# montaj_electric_nou.net
KiCad netlist of a schematic drawn in EAGLE
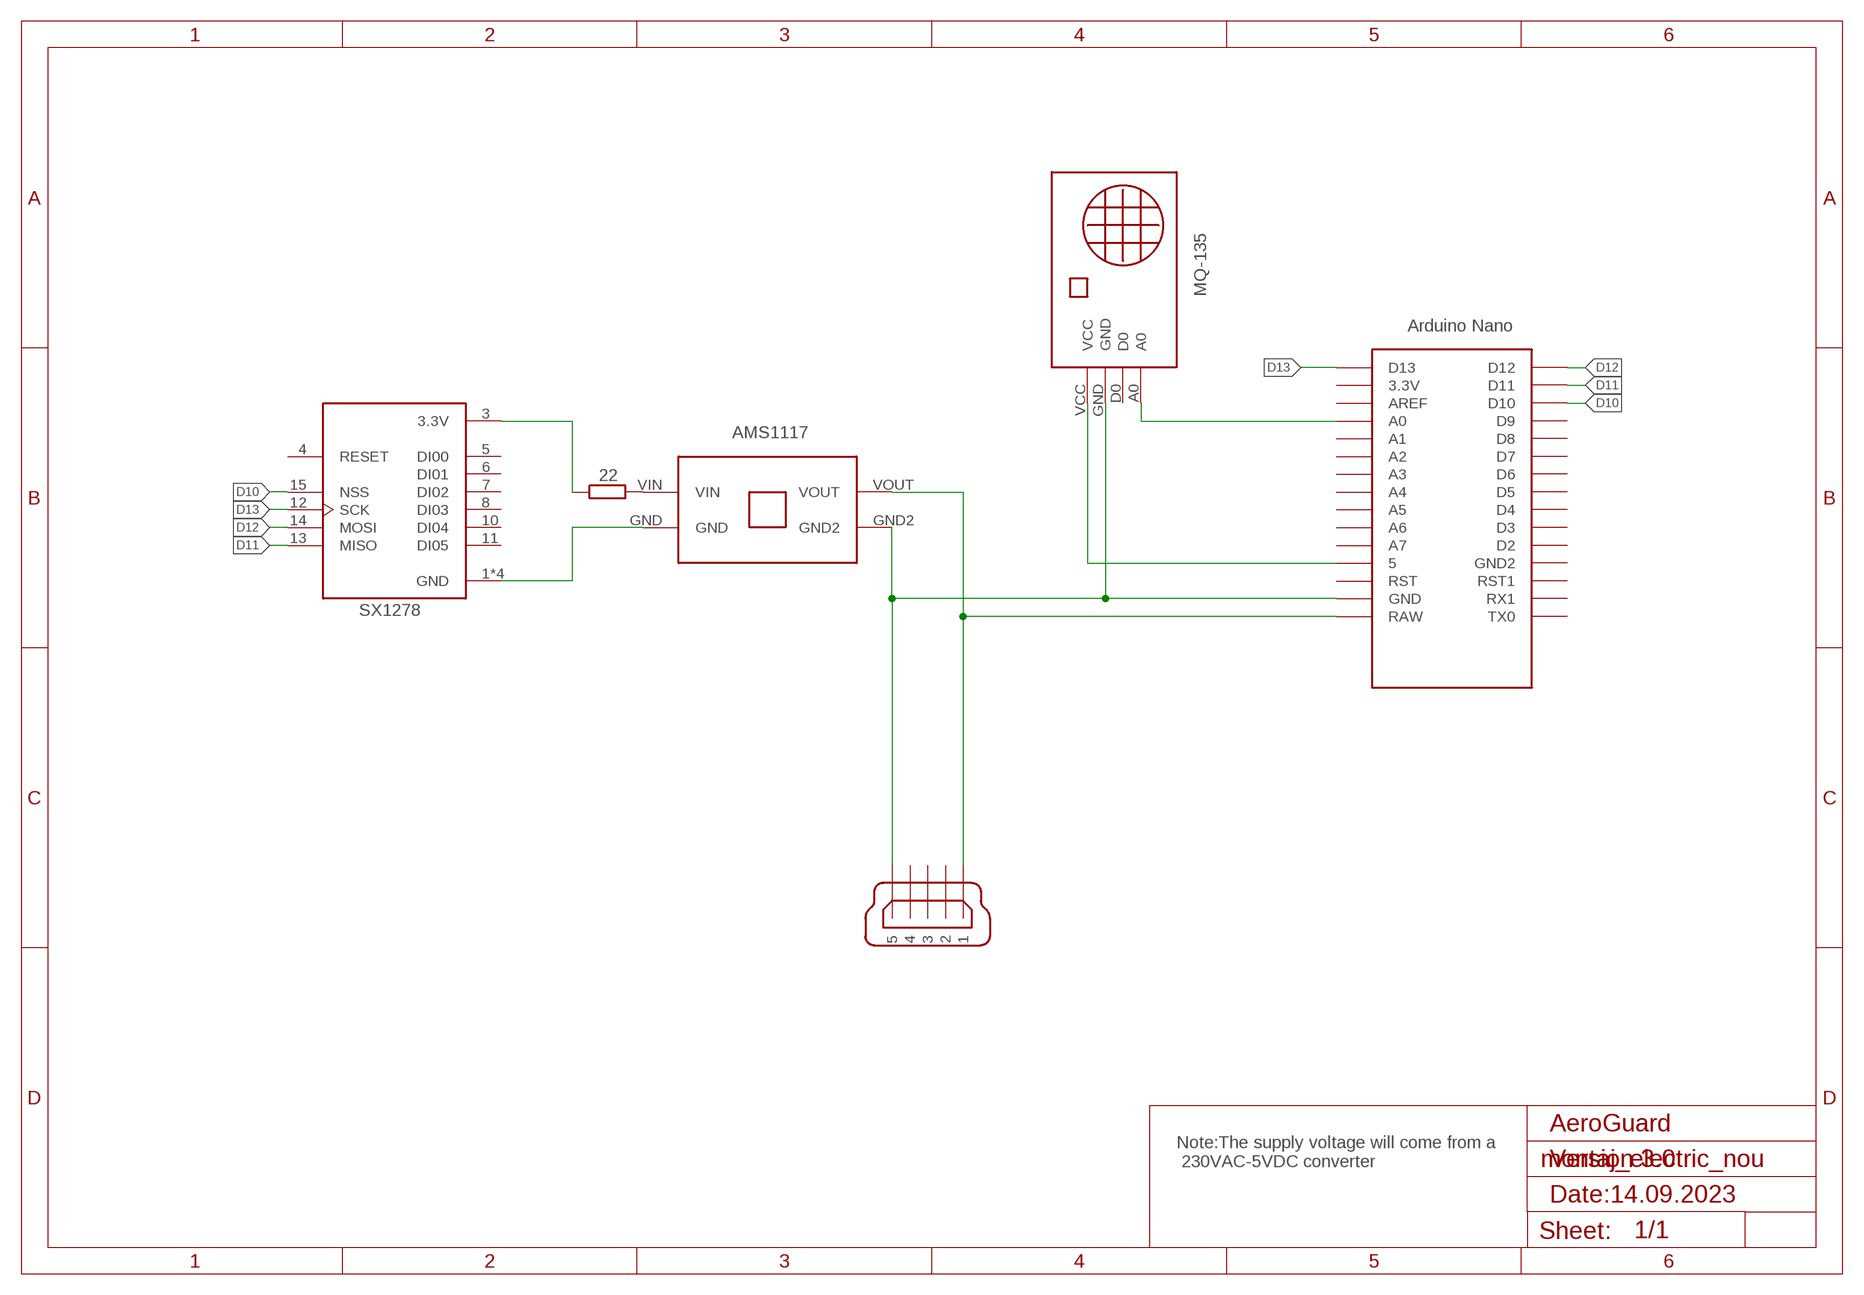
[diagram p0: schematic, sheet 1]

(export (version "E")
  (design (tool "Eeschema 10.0.6"))
  (components
    (comp (ref "22")
      (value "R-EU_0207/12")
      (footprint "eagle-import:0207_12")
      (libsource (lib "eagle-import") (part "R-EU_0207/12"))
    )
    (comp (ref "U$1")
      (value "NANO")
      (footprint "eagle-import:NANO")
      (libsource (lib "eagle-import") (part "NANO"))
    )
    (comp (ref "U$2")
      (value "DEV")
      (footprint "eagle-import:FOOT")
      (libsource (lib "eagle-import") (part "DEV"))
    )
    (comp (ref "U$3")
      (value "AMS1117")
      (footprint "eagle-import:AMS1117")
      (libsource (lib "eagle-import") (part "AMS1117"))
    )
    (comp (ref "U1")
      (value "RA-02_LORA")
      (footprint "eagle-import:MODULE_RA-02_LORA")
      (fields (field (name "MF") "AI-Thinker") (field (name "MP") "Ra-02 LoRa"))
      (libsource (lib "eagle-import") (part "RA-02_LORA"))
    )
    (comp (ref "X1")
      (value "MINI-USB-SHIELD-UX60-MB-5S8")
      (footprint "eagle-import:UX60-MB-5S8")
      (libsource (lib "eagle-import") (part "MINI-USB-SHIELD-UX60-MB-5S8"))
    )
  )
  (nets
    (net (code "1") (name "D10") (class "Default")
      (node (ref "U$1") (pin "D10") (pinfunction "D10_D10") (pintype "bidirectional"))
      (node (ref "U1") (pin "15") (pinfunction "NSS_15") (pintype "input"))
    )
    (net (code "2") (name "D11") (class "Default")
      (node (ref "U$1") (pin "D11") (pinfunction "D11_D11") (pintype "bidirectional"))
      (node (ref "U1") (pin "13") (pinfunction "MISO_13") (pintype "output"))
    )
    (net (code "3") (name "D12") (class "Default")
      (node (ref "U$1") (pin "D12") (pinfunction "D12_D12") (pintype "bidirectional"))
      (node (ref "U1") (pin "14") (pinfunction "MOSI_14") (pintype "input"))
    )
    (net (code "4") (name "D13") (class "Default")
      (node (ref "U$1") (pin "D13") (pinfunction "D13_D13") (pintype "bidirectional"))
      (node (ref "U1") (pin "12") (pinfunction "SCK_12") (pintype "input"))
    )
    (net (code "5") (name "Net-(22-Pad2)") (class "Default")
      (node (ref "22") (pin "2") (pinfunction "2_2") (pintype "passive"))
      (node (ref "U$3") (pin "VIN") (pinfunction "VIN_VIN") (pintype "bidirectional"))
    )
    (net (code "6") (name "Net-(U$1-5)") (class "Default")
      (node (ref "U$1") (pin "5V") (pinfunction "5_5V") (pintype "bidirectional"))
      (node (ref "U$2") (pin "VCC") (pinfunction "VCC_VCC") (pintype "bidirectional"))
    )
    (net (code "7") (name "Net-(U$1-PadA0)") (class "Default")
      (node (ref "U$1") (pin "A0") (pinfunction "A0_A0") (pintype "bidirectional"))
      (node (ref "U$2") (pin "A0") (pinfunction "A0_A0") (pintype "bidirectional"))
    )
    (net (code "8") (name "Net-(U$1-PadGND)") (class "Default")
      (node (ref "U$1") (pin "GND") (pinfunction "GND_GND") (pintype "bidirectional"))
      (node (ref "U$2") (pin "GND") (pinfunction "GND_GND") (pintype "bidirectional"))
      (node (ref "U$3") (pin "GND2") (pinfunction "GND2_GND2") (pintype "bidirectional"))
      (node (ref "X1") (pin "5") (pinfunction "5_5") (pintype "input"))
    )
    (net (code "9") (name "Net-(U$1-PadRAW)") (class "Default")
      (node (ref "U$1") (pin "RAW") (pinfunction "RAW_RAW") (pintype "bidirectional"))
      (node (ref "U$3") (pin "VOUT") (pinfunction "VOUT_VOUT") (pintype "bidirectional"))
      (node (ref "X1") (pin "1") (pinfunction "1_1") (pintype "input"))
    )
    (net (code "10") (name "Net-(U$3-PadGND)") (class "Default")
      (node (ref "U$3") (pin "GND") (pinfunction "GND_GND") (pintype "bidirectional"))
      (node (ref "U1") (pin "1") (pinfunction "GND_1") (pintype "power_in"))
      (node (ref "U1") (pin "16") (pinfunction "GND_16") (pintype "power_in"))
      (node (ref "U1") (pin "2") (pinfunction "GND_2") (pintype "power_in"))
      (node (ref "U1") (pin "9") (pinfunction "GND_9") (pintype "power_in"))
    )
    (net (code "11") (name "Net-(U1-3.3V)") (class "Default")
      (node (ref "22") (pin "1") (pinfunction "1_1") (pintype "passive"))
      (node (ref "U1") (pin "3") (pinfunction "3.3V_3") (pintype "power_in"))
    )
    (net (code "12") (name "unconnected-(U$1-GND2-PadGND1)") (class "Default")
      (node (ref "U$1") (pin "GND1") (pinfunction "GND2_GND1") (pintype "bidirectional"))
    )
    (net (code "13") (name "unconnected-(U$1-Pad3.3V)") (class "Default")
      (node (ref "U$1") (pin "3.3V") (pinfunction "3.3V_3.3V") (pintype "bidirectional"))
    )
    (net (code "14") (name "unconnected-(U$1-PadA1)") (class "Default")
      (node (ref "U$1") (pin "A1") (pinfunction "A1_A1") (pintype "bidirectional"))
    )
    (net (code "15") (name "unconnected-(U$1-PadA2)") (class "Default")
      (node (ref "U$1") (pin "A2") (pinfunction "A2_A2") (pintype "bidirectional"))
    )
    (net (code "16") (name "unconnected-(U$1-PadA3)") (class "Default")
      (node (ref "U$1") (pin "A3") (pinfunction "A3_A3") (pintype "bidirectional"))
    )
    (net (code "17") (name "unconnected-(U$1-PadA4)") (class "Default")
      (node (ref "U$1") (pin "A4") (pinfunction "A4_A4") (pintype "bidirectional"))
    )
    (net (code "18") (name "unconnected-(U$1-PadA5)") (class "Default")
      (node (ref "U$1") (pin "A5") (pinfunction "A5_A5") (pintype "bidirectional"))
    )
    (net (code "19") (name "unconnected-(U$1-PadA6)") (class "Default")
      (node (ref "U$1") (pin "A6") (pinfunction "A6_A6") (pintype "bidirectional"))
    )
    (net (code "20") (name "unconnected-(U$1-PadA7)") (class "Default")
      (node (ref "U$1") (pin "A7") (pinfunction "A7_A7") (pintype "bidirectional"))
    )
    (net (code "21") (name "unconnected-(U$1-PadAREF)") (class "Default")
      (node (ref "U$1") (pin "AREF") (pinfunction "AREF_AREF") (pintype "bidirectional"))
    )
    (net (code "22") (name "unconnected-(U$1-PadD2)") (class "Default")
      (node (ref "U$1") (pin "D2") (pinfunction "D2_D2") (pintype "bidirectional"))
    )
    (net (code "23") (name "unconnected-(U$1-PadD3)") (class "Default")
      (node (ref "U$1") (pin "D3") (pinfunction "D3_D3") (pintype "bidirectional"))
    )
    (net (code "24") (name "unconnected-(U$1-PadD4)") (class "Default")
      (node (ref "U$1") (pin "D4") (pinfunction "D4_D4") (pintype "bidirectional"))
    )
    (net (code "25") (name "unconnected-(U$1-PadD5)") (class "Default")
      (node (ref "U$1") (pin "D5") (pinfunction "D5_D5") (pintype "bidirectional"))
    )
    (net (code "26") (name "unconnected-(U$1-PadD6)") (class "Default")
      (node (ref "U$1") (pin "D6") (pinfunction "D6_D6") (pintype "bidirectional"))
    )
    (net (code "27") (name "unconnected-(U$1-PadD7)") (class "Default")
      (node (ref "U$1") (pin "D7") (pinfunction "D7_D7") (pintype "bidirectional"))
    )
    (net (code "28") (name "unconnected-(U$1-PadD8)") (class "Default")
      (node (ref "U$1") (pin "D8") (pinfunction "D8_D8") (pintype "bidirectional"))
    )
    (net (code "29") (name "unconnected-(U$1-PadD9)") (class "Default")
      (node (ref "U$1") (pin "D9") (pinfunction "D9_D9") (pintype "bidirectional"))
    )
    (net (code "30") (name "unconnected-(U$1-PadICSP1)") (class "Default")
      (node (ref "U$1") (pin "ICSP1") (pinfunction "ICSP1_ICSP1") (pintype "bidirectional"))
    )
    (net (code "31") (name "unconnected-(U$1-PadICSP2)") (class "Default")
      (node (ref "U$1") (pin "ICSP2") (pinfunction "ICSP2_ICSP2") (pintype "bidirectional"))
    )
    (net (code "32") (name "unconnected-(U$1-PadICSP3)") (class "Default")
      (node (ref "U$1") (pin "ICSP3") (pinfunction "ICSP3_ICSP3") (pintype "bidirectional"))
    )
    (net (code "33") (name "unconnected-(U$1-PadICSP4)") (class "Default")
      (node (ref "U$1") (pin "ICSP4") (pinfunction "ICSP4_ICSP4") (pintype "bidirectional"))
    )
    (net (code "34") (name "unconnected-(U$1-PadICSP5)") (class "Default")
      (node (ref "U$1") (pin "ICSP5") (pinfunction "ICSP5_ICSP5") (pintype "bidirectional"))
    )
    (net (code "35") (name "unconnected-(U$1-PadICSP6)") (class "Default")
      (node (ref "U$1") (pin "ICSP6") (pinfunction "ICSP6_ICSP6") (pintype "bidirectional"))
    )
    (net (code "36") (name "unconnected-(U$1-PadRST)") (class "Default")
      (node (ref "U$1") (pin "RST") (pinfunction "RST_RST") (pintype "bidirectional"))
    )
    (net (code "37") (name "unconnected-(U$1-PadRST1)") (class "Default")
      (node (ref "U$1") (pin "RST1") (pinfunction "RST1_RST1") (pintype "bidirectional"))
    )
    (net (code "38") (name "unconnected-(U$1-PadRX1)") (class "Default")
      (node (ref "U$1") (pin "RX1") (pinfunction "RX1_RX1") (pintype "bidirectional"))
    )
    (net (code "39") (name "unconnected-(U$1-PadTX0)") (class "Default")
      (node (ref "U$1") (pin "TX0") (pinfunction "TX0_TX0") (pintype "bidirectional"))
    )
    (net (code "40") (name "unconnected-(U$2-PadD0)") (class "Default")
      (node (ref "U$2") (pin "D0") (pinfunction "D0_D0") (pintype "bidirectional"))
    )
    (net (code "41") (name "unconnected-(U1-DI00-Pad5)") (class "Default")
      (node (ref "U1") (pin "5") (pinfunction "DI00_5") (pintype "bidirectional"))
    )
    (net (code "42") (name "unconnected-(U1-DI01-Pad6)") (class "Default")
      (node (ref "U1") (pin "6") (pinfunction "DI01_6") (pintype "bidirectional"))
    )
    (net (code "43") (name "unconnected-(U1-DI02-Pad7)") (class "Default")
      (node (ref "U1") (pin "7") (pinfunction "DI02_7") (pintype "bidirectional"))
    )
    (net (code "44") (name "unconnected-(U1-DI03-Pad8)") (class "Default")
      (node (ref "U1") (pin "8") (pinfunction "DI03_8") (pintype "bidirectional"))
    )
    (net (code "45") (name "unconnected-(U1-DI04-Pad10)") (class "Default")
      (node (ref "U1") (pin "10") (pinfunction "DI04_10") (pintype "bidirectional"))
    )
    (net (code "46") (name "unconnected-(U1-DI05-Pad11)") (class "Default")
      (node (ref "U1") (pin "11") (pinfunction "DI05_11") (pintype "bidirectional"))
    )
    (net (code "47") (name "unconnected-(U1-RESET-Pad4)") (class "Default")
      (node (ref "U1") (pin "4") (pinfunction "RESET_4") (pintype "input"))
    )
    (net (code "48") (name "unconnected-(X1-Pad2)") (class "Default")
      (node (ref "X1") (pin "2") (pinfunction "2_2") (pintype "input"))
    )
    (net (code "49") (name "unconnected-(X1-Pad3)") (class "Default")
      (node (ref "X1") (pin "3") (pinfunction "3_3") (pintype "input"))
    )
    (net (code "50") (name "unconnected-(X1-Pad4)") (class "Default")
      (node (ref "X1") (pin "4") (pinfunction "4_4") (pintype "input"))
    )
  )
)
